# LED_Driver.net
KiCad netlist of a schematic drawn in Altium Designer
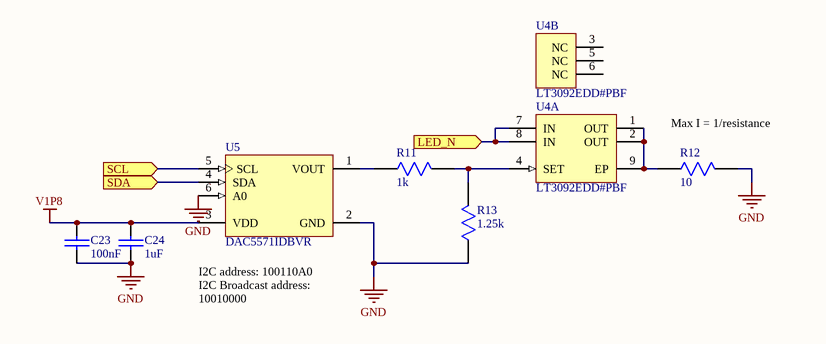
[diagram p0: LED_Driver.SchDoc]

(export (version "E")
  (design (tool "Eeschema 10.0.6"))
  (components
    (comp (ref "C23")
      (value "100nF")
      (footprint "SMD CAP 0402")
      (libsource (lib "DA_Component_Library") (part "Capacitor"))
    )
    (comp (ref "C24")
      (value "1uF")
      (footprint "SMD CAP 0402")
      (libsource (lib "DA_Component_Library") (part "Capacitor"))
    )
    (comp (ref "R11")
      (value "1k")
      (footprint "SMD RES 0402")
      (libsource (lib "DA_Component_Library") (part "Resistor"))
    )
    (comp (ref "R12")
      (value "10")
      (footprint "SMD RES 0402")
      (libsource (lib "DA_Component_Library") (part "Resistor"))
    )
    (comp (ref "R13")
      (value "1.25k")
      (footprint "SMD RES 0402")
      (libsource (lib "DA_Component_Library") (part "Resistor"))
    )
    (comp (ref "U4")
      (value "LT3092EDD#PBF")
      (footprint "LT-DD-8_V")
      (fields (field (name "MANUFACTURER") "Linear Technology"))
      (libsource (lib "Linear Technology Power Management Current Sources") (part "LT3092EDD#PBF"))
    )
    (comp (ref "U5")
      (value "DAC5571IDBVR")
      (footprint "TI-DBV6_M")
      (fields (field (name "MANUFACTURER") "Texas Instruments"))
      (libsource (lib "TI Data Converters Digital to Analog Converter") (part "DAC5571IDBVR"))
    )
  )
  (nets
    (net (code "1") (name "/LED_N") (class "Default")
      (node (ref "U4") (pin "7") (pinfunction "IN_7") (pintype "power_in"))
      (node (ref "U4") (pin "8") (pinfunction "IN_8") (pintype "power_in"))
    )
    (net (code "2") (name "/SCL") (class "Default")
      (node (ref "U5") (pin "5") (pinfunction "SCL_5") (pintype "input"))
    )
    (net (code "3") (name "/SDA") (class "Default")
      (node (ref "U5") (pin "4") (pinfunction "SDA_4") (pintype "input"))
    )
    (net (code "4") (name "GND") (class "Default")
      (node (ref "C23") (pin "1") (pinfunction "1_1") (pintype "passive"))
      (node (ref "C24") (pin "1") (pinfunction "1_1") (pintype "passive"))
      (node (ref "R12") (pin "1") (pinfunction "1_1") (pintype "passive"))
      (node (ref "R13") (pin "0") (pinfunction "0_0") (pintype "passive"))
      (node (ref "U5") (pin "2") (pinfunction "GND_2") (pintype "power_in"))
      (node (ref "U5") (pin "6") (pinfunction "A0_6") (pintype "input"))
    )
    (net (code "5") (name "Net-(U4A-EP)") (class "Default")
      (node (ref "R12") (pin "0") (pinfunction "0_0") (pintype "passive"))
      (node (ref "U4") (pin "1") (pinfunction "OUT_1") (pintype "power_in"))
      (node (ref "U4") (pin "2") (pinfunction "OUT_2") (pintype "power_in"))
      (node (ref "U4") (pin "9") (pinfunction "EP_9") (pintype "power_in"))
    )
    (net (code "6") (name "Net-(U4A-SET)") (class "Default")
      (node (ref "R11") (pin "1") (pinfunction "1_1") (pintype "passive"))
      (node (ref "R13") (pin "1") (pinfunction "1_1") (pintype "passive"))
      (node (ref "U4") (pin "4") (pinfunction "SET_4") (pintype "input"))
    )
    (net (code "7") (name "Net-(U5-VOUT)") (class "Default")
      (node (ref "R11") (pin "0") (pinfunction "0_0") (pintype "passive"))
      (node (ref "U5") (pin "1") (pinfunction "VOUT_1") (pintype "tri_state"))
    )
    (net (code "8") (name "V1P8") (class "Default")
      (node (ref "C23") (pin "0") (pinfunction "0_0") (pintype "passive"))
      (node (ref "C24") (pin "0") (pinfunction "0_0") (pintype "passive"))
      (node (ref "U5") (pin "3") (pinfunction "VDD_3") (pintype "power_in"))
    )
    (net (code "9") (name "unconnected-(U4B-NC-Pad3)") (class "Default")
      (node (ref "U4") (pin "3") (pinfunction "NC_3") (pintype "passive"))
    )
    (net (code "10") (name "unconnected-(U4B-NC-Pad5)") (class "Default")
      (node (ref "U4") (pin "5") (pinfunction "NC_5") (pintype "passive"))
    )
    (net (code "11") (name "unconnected-(U4B-NC-Pad6)") (class "Default")
      (node (ref "U4") (pin "6") (pinfunction "NC_6") (pintype "passive"))
    )
  )
)
